# Charger.net
KiCad netlist of a schematic drawn in Altium Designer
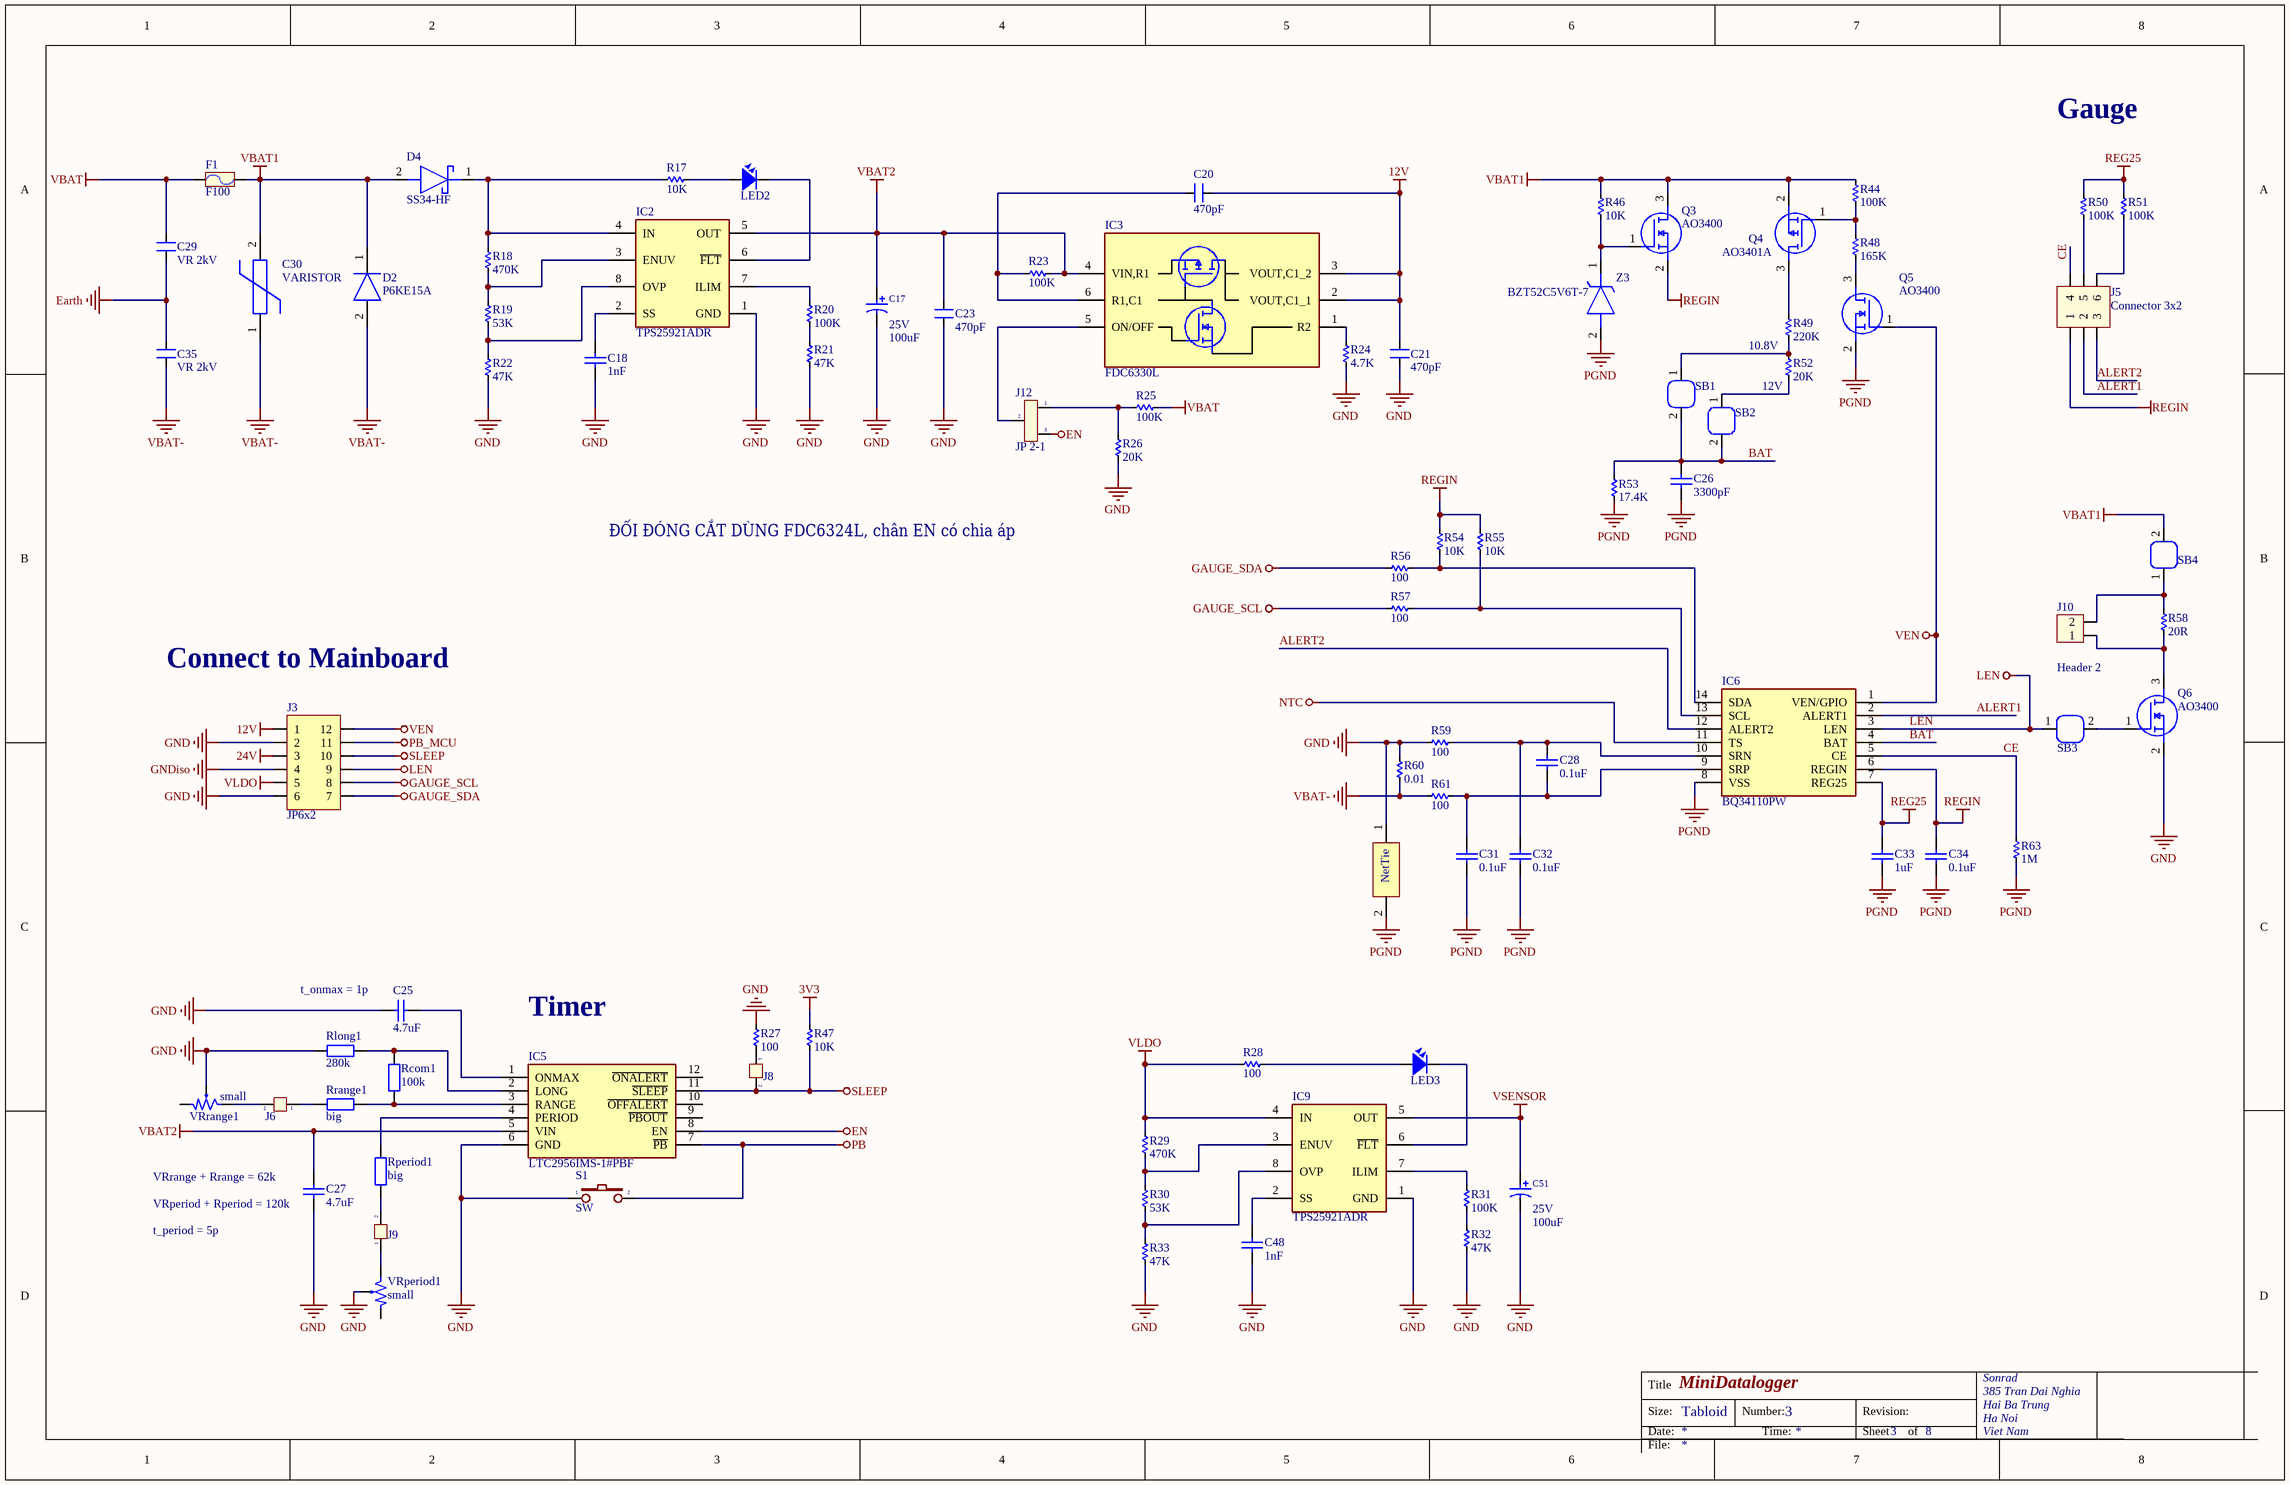
[diagram p0: Charger.SchDoc]

(export (version "E")
  (design (tool "Eeschema 10.0.6"))
  (components
    (comp (ref "*") (value "NetTie") (footprint "NetTie") (libsource (lib "PhanBach") (part "NetTie")))
    (comp (ref "C17")
      (value "100uF")
      (footprint "Cap SMD Tant")
      (description "Polarized Tanta Capacitor")
      (fields
        (field (name "MANUFACTURER") "FARNELL")
        (field (name "VOLT") "25V")
        (field (name "Comment") "100 uF 25V")
        (field (name "PUBLISHER") "Hoang Nguyen")
      )
      (libsource (lib "hphonglib") (part "Cap_Pol"))
    )
    (comp (ref "C18")
      (value "1nF")
      (footprint "0805 CAP")
      (fields (field (name "PUBLISHER") "Altium Limited"))
      (libsource (lib "ThinhNguyenLib") (part "CAP CERAMIC"))
    )
    (comp (ref "C20")
      (value "470pF")
      (footprint "SM-0805")
      (description "Cap SMD")
      (libsource (lib "hphonglib") (part "CM"))
    )
    (comp (ref "C21")
      (value "470pF")
      (footprint "SM-0805")
      (description "Cap SMD")
      (libsource (lib "hphonglib") (part "CM"))
    )
    (comp (ref "C23")
      (value "470pF")
      (footprint "SM-0805")
      (description "Cap SMD")
      (libsource (lib "hphonglib") (part "CM"))
    )
    (comp (ref "C25")
      (value "4.7uF")
      (footprint "0805 CAP")
      (fields (field (name "PUBLISHER") "Altium Limited"))
      (libsource (lib "ThinhNguyenLib") (part "CAP CERAMIC"))
    )
    (comp (ref "C26")
      (value "3300pF")
      (footprint "0805 CAP")
      (fields (field (name "PUBLISHER") "Altium Limited"))
      (libsource (lib "ThinhNguyenLib") (part "CAP CERAMIC"))
    )
    (comp (ref "C27")
      (value "4.7uF")
      (footprint "0805 CAP")
      (fields (field (name "PUBLISHER") "Altium Limited"))
      (libsource (lib "ThinhNguyenLib") (part "CAP CERAMIC"))
    )
    (comp (ref "C28")
      (value "0.1uF")
      (footprint "0805 CAP")
      (fields (field (name "PUBLISHER") "Altium Limited"))
      (libsource (lib "ThinhNguyenLib") (part "CAP CERAMIC"))
    )
    (comp (ref "C29")
      (value "VR 2kV")
      (footprint "CN3")
      (description "MOV")
      (fields (field (name "COPYRIGHT") "VanDungEvn"))
      (libsource (lib "library") (part "CN3"))
    )
    (comp (ref "C30")
      (value "VARISTOR")
      (footprint "CN2")
      (libsource (lib "ThinhNguyenLib") (part "VARISTOR"))
    )
    (comp (ref "C31")
      (value "0.1uF")
      (footprint "0805 CAP")
      (fields (field (name "PUBLISHER") "Altium Limited"))
      (libsource (lib "ThinhNguyenLib") (part "CAP CERAMIC"))
    )
    (comp (ref "C32")
      (value "0.1uF")
      (footprint "0805 CAP")
      (fields (field (name "PUBLISHER") "Altium Limited"))
      (libsource (lib "ThinhNguyenLib") (part "CAP CERAMIC"))
    )
    (comp (ref "C33")
      (value "1uF")
      (footprint "0805 CAP")
      (fields (field (name "PUBLISHER") "Altium Limited"))
      (libsource (lib "ThinhNguyenLib") (part "CAP CERAMIC"))
    )
    (comp (ref "C34")
      (value "0.1uF")
      (footprint "0805 CAP")
      (fields (field (name "PUBLISHER") "Altium Limited"))
      (libsource (lib "ThinhNguyenLib") (part "CAP CERAMIC"))
    )
    (comp (ref "C35")
      (value "VR 2kV")
      (footprint "CN3")
      (description "MOV")
      (fields (field (name "COPYRIGHT") "VanDungEvn"))
      (libsource (lib "library") (part "CN3"))
    )
    (comp (ref "C48")
      (value "1nF")
      (footprint "0805 CAP")
      (fields (field (name "PUBLISHER") "Altium Limited"))
      (libsource (lib "ThinhNguyenLib") (part "CAP CERAMIC"))
    )
    (comp (ref "C51")
      (value "100uF")
      (footprint "Cap SMD Tant")
      (description "Polarized Tanta Capacitor")
      (fields
        (field (name "MANUFACTURER") "FARNELL")
        (field (name "VOLT") "25V")
        (field (name "Comment") "100 uF 25V")
        (field (name "PUBLISHER") "Hoang Nguyen")
      )
      (libsource (lib "hphonglib") (part "Cap_Pol"))
    )
    (comp (ref "D2")
      (value "P6KE15A")
      (footprint "P6KE15A")
      (description "Diode")
      (fields (field (name "MOUSER PART NUMBER") "511-P6KE15A"))
      (libsource (lib "*") (part "P6KE15A"))
    )
    (comp (ref "D4")
      (value "SS34-HF")
      (footprint "SamacSys:DIOM5025X220N")
      (description "Schottky Diode")
      (fields (field (name "MOUSER PART NUMBER") "750-SS34-HF"))
      (libsource (lib "SamacSys") (part "SS34-HF"))
    )
    (comp (ref "F1")
      (value "F100")
      (footprint "Fuse1A")
      (description "Fuse")
      (fields (field (name "DESIGNED BY") "VanDungEvn"))
      (libsource (lib "HMI") (part "Fuse"))
    )
    (comp (ref "IC2")
      (value "TPS25921ADR")
      (footprint "SamacSys:SOIC127P600X175-8N")
      (description "Integrated Circuit")
      (fields (field (name "MOUSER PART NUMBER") "595-TPS25921ADR"))
      (libsource (lib "SamacSys") (part "TPS25921ADR"))
    )
    (comp (ref "IC3")
      (value "FDC6330L")
      (footprint "SamacSys:SOT95P280X110-6N")
      (description "Integrated Circuit")
      (fields (field (name "MOUSER PART NUMBER") "512-FDC6330L"))
      (libsource (lib "SamacSys") (part "FDC6330L"))
    )
    (comp (ref "IC5")
      (value "LTC2956IMS-1#PBF")
      (footprint "SamacSys:SOP65P490X110-12N")
      (description "Integrated Circuit")
      (fields (field (name "MOUSER PART NUMBER") "584-LTC2956IMS-1#PBF"))
      (libsource (lib "*") (part "LTC2956IMS-1#PBF"))
    )
    (comp (ref "IC6")
      (value "BQ34110PW")
      (footprint "SamacSys:SOP65P640X120-14N")
      (description "Integrated Circuit")
      (fields (field (name "MOUSER PART NUMBER") "595-BQ34110PW"))
      (libsource (lib "*") (part "BQ34110PW"))
    )
    (comp (ref "IC9")
      (value "TPS25921ADR")
      (footprint "SamacSys:SOIC127P600X175-8N")
      (description "Integrated Circuit")
      (fields (field (name "MOUSER PART NUMBER") "595-TPS25921ADR"))
      (libsource (lib "SamacSys") (part "TPS25921ADR"))
    )
    (comp (ref "J3")
      (value "JP6x2")
      (footprint "JP6-D2T")
      (description "WR-PHD 2.54 mm Dual Socket Header")
      (fields
        (field (name "MANUFACTURER") "Würth Elektronik eiSos GmbH")
        (field (name "PARTNO") "61301221821")
        (field (name "CREATED BY") "Karrer Zheng")
      )
      (libsource (lib "LIBRARY1") (part "JP6x2"))
    )
    (comp (ref "J5")
      (value "Connector 3x2")
      (footprint "JP3x2")
      (libsource (lib "syhaunguyen") (part "JP3x2"))
    )
    (comp (ref "J6") (value "Jumper 2") (footprint "JP2") (libsource (lib "library") (part "JP 2")))
    (comp (ref "J8") (value "Jumper 2") (footprint "JP2") (libsource (lib "") (part "JP 2_2")))
    (comp (ref "J9") (value "Jumper 2") (footprint "JP2") (libsource (lib "") (part "JP 2_1")))
    (comp (ref "J10")
      (value "Header 2")
      (footprint "HED2B")
      (description "Header 2 (Green)")
      (libsource (lib "syhaunguyen") (part "Hed2"))
    )
    (comp (ref "J12")
      (value "JP 2-1")
      (footprint "JP3")
      (description "Jumper 2-1")
      (libsource (lib "syhaunguyen") (part "JP 2-1"))
    )
    (comp (ref "LED2") (value "LED") (footprint "LED 3512") (libsource (lib "LIBRARY1") (part "LED SMD")))
    (comp (ref "LED3") (value "LED") (footprint "LED 3512") (libsource (lib "LIBRARY1") (part "LED SMD")))
    (comp (ref "Q3")
      (value "AO3400")
      (footprint "SamacSys:SOT95P280X125-3N")
      (description "MOSFET (N-Channel)")
      (libsource (lib "*") (part "AO3400"))
    )
    (comp (ref "Q4")
      (value "AO3401A")
      (footprint "SamacSys:SOT95P280X125-3N")
      (description "MOSFET (P-Channel)")
      (libsource (lib "*") (part "AO3401A"))
    )
    (comp (ref "Q5")
      (value "AO3400")
      (footprint "SamacSys:SOT95P280X125-3N")
      (description "MOSFET (N-Channel)")
      (libsource (lib "*") (part "AO3400"))
    )
    (comp (ref "Q6")
      (value "AO3400")
      (footprint "SamacSys:SOT95P280X125-3N")
      (description "MOSFET (N-Channel)")
      (libsource (lib "*") (part "AO3400"))
    )
    (comp (ref "R17")
      (value "10K")
      (footprint "RES-SMD-0805")
      (description "Resistor")
      (fields
        (field (name "MANUFACTURER") "Generic Components")
        (field (name "PUBLISHER") "Altium Hobart Technology Centre")
      )
      (libsource (lib "LIBRARY1") (part "Res-SMD"))
    )
    (comp (ref "R18")
      (value "470K")
      (footprint "RES-SMD-0805")
      (description "Resistor")
      (fields
        (field (name "MANUFACTURER") "Generic Components")
        (field (name "PUBLISHER") "Altium Hobart Technology Centre")
      )
      (libsource (lib "LIBRARY1") (part "Res-SMD"))
    )
    (comp (ref "R19")
      (value "53K")
      (footprint "RES-SMD-0805")
      (description "Resistor")
      (fields
        (field (name "MANUFACTURER") "Generic Components")
        (field (name "PUBLISHER") "Altium Hobart Technology Centre")
      )
      (libsource (lib "LIBRARY1") (part "Res-SMD"))
    )
    (comp (ref "R20")
      (value "100K")
      (footprint "RES-SMD-0805")
      (description "Resistor")
      (fields
        (field (name "MANUFACTURER") "Generic Components")
        (field (name "PUBLISHER") "Altium Hobart Technology Centre")
      )
      (libsource (lib "LIBRARY1") (part "Res-SMD"))
    )
    (comp (ref "R21")
      (value "47K")
      (footprint "RES-SMD-0805")
      (description "Resistor")
      (fields
        (field (name "MANUFACTURER") "Generic Components")
        (field (name "PUBLISHER") "Altium Hobart Technology Centre")
      )
      (libsource (lib "LIBRARY1") (part "Res-SMD"))
    )
    (comp (ref "R22")
      (value "47K")
      (footprint "RES-SMD-0805")
      (description "Resistor")
      (fields
        (field (name "MANUFACTURER") "Generic Components")
        (field (name "PUBLISHER") "Altium Hobart Technology Centre")
      )
      (libsource (lib "LIBRARY1") (part "Res-SMD"))
    )
    (comp (ref "R23")
      (value "100K")
      (footprint "RES-SMD-0805")
      (description "Resistor")
      (fields
        (field (name "MANUFACTURER") "Generic Components")
        (field (name "PUBLISHER") "Altium Hobart Technology Centre")
      )
      (libsource (lib "LIBRARY1") (part "Res-SMD"))
    )
    (comp (ref "R24")
      (value "4.7K")
      (footprint "RES-SMD-0805")
      (description "Resistor")
      (fields
        (field (name "MANUFACTURER") "Generic Components")
        (field (name "PUBLISHER") "Altium Hobart Technology Centre")
      )
      (libsource (lib "LIBRARY1") (part "Res-SMD"))
    )
    (comp (ref "R25")
      (value "100K")
      (footprint "RES-SMD-0805")
      (description "Resistor")
      (fields
        (field (name "MANUFACTURER") "Generic Components")
        (field (name "PUBLISHER") "Altium Hobart Technology Centre")
      )
      (libsource (lib "LIBRARY1") (part "Res-SMD"))
    )
    (comp (ref "R26")
      (value "20K")
      (footprint "RES-SMD-0805")
      (description "Resistor")
      (fields
        (field (name "MANUFACTURER") "Generic Components")
        (field (name "PUBLISHER") "Altium Hobart Technology Centre")
      )
      (libsource (lib "LIBRARY1") (part "Res-SMD"))
    )
    (comp (ref "R27")
      (value "100")
      (footprint "RES-SMD-0805")
      (description "Resistor")
      (fields
        (field (name "MANUFACTURER") "Generic Components")
        (field (name "PUBLISHER") "Altium Hobart Technology Centre")
      )
      (libsource (lib "LIBRARY1") (part "Res-SMD"))
    )
    (comp (ref "R28")
      (value "100")
      (footprint "RES-SMD-0805")
      (description "Resistor")
      (fields
        (field (name "MANUFACTURER") "Generic Components")
        (field (name "PUBLISHER") "Altium Hobart Technology Centre")
      )
      (libsource (lib "LIBRARY1") (part "Res-SMD"))
    )
    (comp (ref "R29")
      (value "470K")
      (footprint "RES-SMD-0805")
      (description "Resistor")
      (fields
        (field (name "MANUFACTURER") "Generic Components")
        (field (name "PUBLISHER") "Altium Hobart Technology Centre")
      )
      (libsource (lib "LIBRARY1") (part "Res-SMD"))
    )
    (comp (ref "R30")
      (value "53K")
      (footprint "RES-SMD-0805")
      (description "Resistor")
      (fields
        (field (name "MANUFACTURER") "Generic Components")
        (field (name "PUBLISHER") "Altium Hobart Technology Centre")
      )
      (libsource (lib "LIBRARY1") (part "Res-SMD"))
    )
    (comp (ref "R31")
      (value "100K")
      (footprint "RES-SMD-0805")
      (description "Resistor")
      (fields
        (field (name "MANUFACTURER") "Generic Components")
        (field (name "PUBLISHER") "Altium Hobart Technology Centre")
      )
      (libsource (lib "LIBRARY1") (part "Res-SMD"))
    )
    (comp (ref "R32")
      (value "47K")
      (footprint "RES-SMD-0805")
      (description "Resistor")
      (fields
        (field (name "MANUFACTURER") "Generic Components")
        (field (name "PUBLISHER") "Altium Hobart Technology Centre")
      )
      (libsource (lib "LIBRARY1") (part "Res-SMD"))
    )
    (comp (ref "R33")
      (value "47K")
      (footprint "RES-SMD-0805")
      (description "Resistor")
      (fields
        (field (name "MANUFACTURER") "Generic Components")
        (field (name "PUBLISHER") "Altium Hobart Technology Centre")
      )
      (libsource (lib "LIBRARY1") (part "Res-SMD"))
    )
    (comp (ref "R44")
      (value "100K")
      (footprint "RES-SMD-0805")
      (description "Resistor")
      (fields
        (field (name "MANUFACTURER") "Generic Components")
        (field (name "PUBLISHER") "Altium Hobart Technology Centre")
      )
      (libsource (lib "LIBRARY1") (part "Res-SMD"))
    )
    (comp (ref "R46")
      (value "10K")
      (footprint "RES-SMD-0805")
      (description "Resistor")
      (fields
        (field (name "MANUFACTURER") "Generic Components")
        (field (name "PUBLISHER") "Altium Hobart Technology Centre")
      )
      (libsource (lib "LIBRARY1") (part "Res-SMD"))
    )
    (comp (ref "R47")
      (value "10K")
      (footprint "RES-SMD-0805")
      (description "Resistor")
      (fields
        (field (name "MANUFACTURER") "Generic Components")
        (field (name "PUBLISHER") "Altium Hobart Technology Centre")
      )
      (libsource (lib "LIBRARY1") (part "Res-SMD"))
    )
    (comp (ref "R48")
      (value "165K")
      (footprint "RES-SMD-0805")
      (description "Resistor")
      (fields
        (field (name "MANUFACTURER") "Generic Components")
        (field (name "PUBLISHER") "Altium Hobart Technology Centre")
      )
      (libsource (lib "LIBRARY1") (part "Res-SMD"))
    )
    (comp (ref "R49")
      (value "220K")
      (footprint "RES-SMD-0805")
      (description "Resistor")
      (fields
        (field (name "MANUFACTURER") "Generic Components")
        (field (name "PUBLISHER") "Altium Hobart Technology Centre")
      )
      (libsource (lib "LIBRARY1") (part "Res-SMD"))
    )
    (comp (ref "R50")
      (value "100K")
      (footprint "RES-SMD-0805")
      (description "Resistor")
      (fields
        (field (name "MANUFACTURER") "Generic Components")
        (field (name "PUBLISHER") "Altium Hobart Technology Centre")
      )
      (libsource (lib "LIBRARY1") (part "Res-SMD"))
    )
    (comp (ref "R51")
      (value "100K")
      (footprint "RES-SMD-0805")
      (description "Resistor")
      (fields
        (field (name "MANUFACTURER") "Generic Components")
        (field (name "PUBLISHER") "Altium Hobart Technology Centre")
      )
      (libsource (lib "LIBRARY1") (part "Res-SMD"))
    )
    (comp (ref "R52")
      (value "20K")
      (footprint "RES-SMD-0805")
      (description "Resistor")
      (fields
        (field (name "MANUFACTURER") "Generic Components")
        (field (name "PUBLISHER") "Altium Hobart Technology Centre")
      )
      (libsource (lib "LIBRARY1") (part "Res-SMD"))
    )
    (comp (ref "R53")
      (value "17.4K")
      (footprint "RES-SMD-0805")
      (description "Resistor")
      (fields
        (field (name "MANUFACTURER") "Generic Components")
        (field (name "PUBLISHER") "Altium Hobart Technology Centre")
      )
      (libsource (lib "LIBRARY1") (part "Res-SMD"))
    )
    (comp (ref "R54")
      (value "10K")
      (footprint "RES-SMD-0805")
      (description "Resistor")
      (fields
        (field (name "MANUFACTURER") "Generic Components")
        (field (name "PUBLISHER") "Altium Hobart Technology Centre")
      )
      (libsource (lib "LIBRARY1") (part "Res-SMD"))
    )
    (comp (ref "R55")
      (value "10K")
      (footprint "RES-SMD-0805")
      (description "Resistor")
      (fields
        (field (name "MANUFACTURER") "Generic Components")
        (field (name "PUBLISHER") "Altium Hobart Technology Centre")
      )
      (libsource (lib "LIBRARY1") (part "Res-SMD"))
    )
    (comp (ref "R56")
      (value "100")
      (footprint "RES-SMD-0805")
      (description "Resistor")
      (fields
        (field (name "MANUFACTURER") "Generic Components")
        (field (name "PUBLISHER") "Altium Hobart Technology Centre")
      )
      (libsource (lib "LIBRARY1") (part "Res-SMD"))
    )
    (comp (ref "R57")
      (value "100")
      (footprint "RES-SMD-0805")
      (description "Resistor")
      (fields
        (field (name "MANUFACTURER") "Generic Components")
        (field (name "PUBLISHER") "Altium Hobart Technology Centre")
      )
      (libsource (lib "LIBRARY1") (part "Res-SMD"))
    )
    (comp (ref "R58")
      (value "20R")
      (footprint "RES-SMD-2512")
      (description "Resistor")
      (fields
        (field (name "MANUFACTURER") "Generic Components")
        (field (name "PUBLISHER") "Altium Hobart Technology Centre")
      )
      (libsource (lib "LIBRARY1") (part "Res-SMD"))
    )
    (comp (ref "R59")
      (value "100")
      (footprint "RES-SMD-0805")
      (description "Resistor")
      (fields
        (field (name "MANUFACTURER") "Generic Components")
        (field (name "PUBLISHER") "Altium Hobart Technology Centre")
      )
      (libsource (lib "LIBRARY1") (part "Res-SMD"))
    )
    (comp (ref "R60")
      (value "0.01")
      (footprint "RES-SMD-1210")
      (description "Resistor")
      (fields
        (field (name "MANUFACTURER") "Generic Components")
        (field (name "PUBLISHER") "Altium Hobart Technology Centre")
      )
      (libsource (lib "LIBRARY1") (part "Res-SMD"))
    )
    (comp (ref "R61")
      (value "100")
      (footprint "RES-SMD-0805")
      (description "Resistor")
      (fields
        (field (name "MANUFACTURER") "Generic Components")
        (field (name "PUBLISHER") "Altium Hobart Technology Centre")
      )
      (libsource (lib "LIBRARY1") (part "Res-SMD"))
    )
    (comp (ref "R63")
      (value "1M")
      (footprint "RES-SMD-0805")
      (description "Resistor")
      (fields
        (field (name "MANUFACTURER") "Generic Components")
        (field (name "PUBLISHER") "Altium Hobart Technology Centre")
      )
      (libsource (lib "LIBRARY1") (part "Res-SMD"))
    )
    (comp (ref "Rcom1")
      (value "100k")
      (footprint "0805 RESISTOR")
      (libsource (lib "ThinhNguyenLib") (part "RESISTOR"))
    )
    (comp (ref "Rlong1")
      (value "280k")
      (footprint "0805 RESISTOR")
      (libsource (lib "ThinhNguyenLib") (part "RESISTOR"))
    )
    (comp (ref "Rperiod1")
      (value "big")
      (footprint "0805 RESISTOR")
      (libsource (lib "ThinhNguyenLib") (part "RESISTOR"))
    )
    (comp (ref "Rrange1")
      (value "big")
      (footprint "0805 RESISTOR")
      (libsource (lib "ThinhNguyenLib") (part "RESISTOR"))
    )
    (comp (ref "S1")
      (value "SW")
      (footprint "SW2")
      (description "Switch button 2 pin")
      (libsource (lib "library") (part "SW2"))
    )
    (comp (ref "SB1")
      (value "Solder bridge")
      (footprint "Solder Bridge")
      (libsource (lib "PhanBach") (part "Solder bridge"))
    )
    (comp (ref "SB2")
      (value "Solder bridge")
      (footprint "Solder Bridge")
      (libsource (lib "PhanBach") (part "Solder bridge"))
    )
    (comp (ref "SB3")
      (value "Solder bridge")
      (footprint "Solder Bridge")
      (libsource (lib "PhanBach") (part "Solder bridge"))
    )
    (comp (ref "SB4")
      (value "Solder bridge")
      (footprint "Solder Bridge")
      (libsource (lib "PhanBach") (part "Solder bridge"))
    )
    (comp (ref "VRperiod1")
      (value "small")
      (footprint "VR1")
      (description "Var Resistor")
      (libsource (lib "library") (part "VR1"))
    )
    (comp (ref "VRrange1")
      (value "small")
      (footprint "VR1")
      (description "Var Resistor")
      (libsource (lib "library") (part "VR1"))
    )
    (comp (ref "Z3")
      (value "BZT52C5V6T-7")
      (footprint "SamacSys:SODFL1608X65N")
      (description "Zener Diode")
      (fields (field (name "MOUSER PART NUMBER") "621-BZT52C5V6T-7"))
      (libsource (lib "*") (part "BZT52C5V6T-7"))
    )
  )
  (nets
    (net (code "1") (name "/ALERT1") (class "Default")
      (node (ref "IC6") (pin "2") (pinfunction "ALERT1_2") (pintype "passive"))
      (node (ref "J5") (pin "5") (pinfunction "2_5") (pintype "passive"))
    )
    (net (code "2") (name "/ALERT2") (class "Default")
      (node (ref "IC6") (pin "12") (pinfunction "ALERT2_12") (pintype "passive"))
      (node (ref "J5") (pin "6") (pinfunction "3_6") (pintype "passive"))
    )
    (net (code "3") (name "/BAT") (class "Default")
      (node (ref "C26") (pin "2") (pinfunction "2_2") (pintype "passive"))
      (node (ref "IC6") (pin "4") (pinfunction "BAT_4") (pintype "passive"))
      (node (ref "R53") (pin "2") (pinfunction "2_2") (pintype "passive"))
      (node (ref "SB1") (pin "2") (pinfunction "42_2") (pintype "passive"))
      (node (ref "SB2") (pin "2") (pinfunction "42_2") (pintype "passive"))
    )
    (net (code "4") (name "/CE") (class "Default")
      (node (ref "IC6") (pin "5") (pinfunction "CE_5") (pintype "passive"))
      (node (ref "J5") (pin "4") (pinfunction "4_4") (pintype "passive"))
      (node (ref "R63") (pin "2") (pinfunction "2_2") (pintype "passive"))
    )
    (net (code "5") (name "3V3") (class "Default")
      (node (ref "R47") (pin "2") (pinfunction "2_2") (pintype "passive"))
    )
    (net (code "6") (name "12V") (class "Default")
      (node (ref "C20") (pin "2") (pinfunction "2_2") (pintype "passive"))
      (node (ref "C21") (pin "1") (pinfunction "1_1") (pintype "passive"))
      (node (ref "IC3") (pin "2") (pinfunction "VOUT,C1_1_2") (pintype "passive"))
      (node (ref "IC3") (pin "3") (pinfunction "VOUT,C1_2_3") (pintype "passive"))
      (node (ref "J3") (pin "1") (pinfunction "1_1") (pintype "passive"))
    )
    (net (code "7") (name "24V") (class "Default")
      (node (ref "J3") (pin "3") (pinfunction "3_3") (pintype "passive"))
    )
    (net (code "8") (name "EN") (class "Default")
      (node (ref "IC5") (pin "8") (pinfunction "EN_8") (pintype "passive"))
      (node (ref "J12") (pin "3") (pinfunction "3_3") (pintype "passive"))
    )
    (net (code "9") (name "Earth") (class "Default")
      (node (ref "C29") (pin "1") (pinfunction "1_1") (pintype "passive"))
      (node (ref "C35") (pin "2") (pinfunction "2_2") (pintype "passive"))
    )
    (net (code "10") (name "GAUGE_SCL") (class "Default")
      (node (ref "J3") (pin "8") (pinfunction "8_8") (pintype "passive"))
      (node (ref "R57") (pin "1") (pinfunction "1_1") (pintype "passive"))
    )
    (net (code "11") (name "GAUGE_SDA") (class "Default")
      (node (ref "J3") (pin "7") (pinfunction "7_7") (pintype "passive"))
      (node (ref "R56") (pin "1") (pinfunction "1_1") (pintype "passive"))
    )
    (net (code "12") (name "GND") (class "Default")
      (node (ref "*") (pin "1") (pinfunction "43_1") (pintype "passive"))
      (node (ref "C17") (pin "2") (pinfunction "2_2") (pintype "passive"))
      (node (ref "C18") (pin "2") (pinfunction "2_2") (pintype "passive"))
      (node (ref "C21") (pin "2") (pinfunction "2_2") (pintype "passive"))
      (node (ref "C23") (pin "2") (pinfunction "2_2") (pintype "passive"))
      (node (ref "C25") (pin "2") (pinfunction "2_2") (pintype "passive"))
      (node (ref "C27") (pin "1") (pinfunction "1_1") (pintype "passive"))
      (node (ref "C48") (pin "2") (pinfunction "2_2") (pintype "passive"))
      (node (ref "C51") (pin "2") (pinfunction "2_2") (pintype "passive"))
      (node (ref "IC2") (pin "1") (pinfunction "GND_1") (pintype "passive"))
      (node (ref "IC5") (pin "6") (pinfunction "GND_6") (pintype "passive"))
      (node (ref "IC9") (pin "1") (pinfunction "GND_1") (pintype "passive"))
      (node (ref "J3") (pin "2") (pinfunction "2_2") (pintype "passive"))
      (node (ref "J3") (pin "6") (pinfunction "6_6") (pintype "passive"))
      (node (ref "Q6") (pin "2") (pinfunction "S_2") (pintype "passive"))
      (node (ref "R21") (pin "1") (pinfunction "1_1") (pintype "passive"))
      (node (ref "R22") (pin "1") (pinfunction "1_1") (pintype "passive"))
      (node (ref "R24") (pin "1") (pinfunction "1_1") (pintype "passive"))
      (node (ref "R26") (pin "1") (pinfunction "1_1") (pintype "passive"))
      (node (ref "R27") (pin "2") (pinfunction "2_2") (pintype "passive"))
      (node (ref "R32") (pin "1") (pinfunction "1_1") (pintype "passive"))
      (node (ref "R33") (pin "1") (pinfunction "1_1") (pintype "passive"))
      (node (ref "R59") (pin "1") (pinfunction "1_1") (pintype "passive"))
      (node (ref "R60") (pin "1") (pinfunction "1_1") (pintype "passive"))
      (node (ref "Rlong1") (pin "1") (pinfunction "1_1") (pintype "passive"))
      (node (ref "S1") (pin "1") (pinfunction "1_1") (pintype "passive"))
      (node (ref "VRperiod1") (pin "2") (pinfunction "2_2") (pintype "passive"))
      (node (ref "VRrange1") (pin "2") (pinfunction "2_2") (pintype "passive"))
    )
    (net (code "13") (name "GNDiso") (class "Default")
      (node (ref "J3") (pin "4") (pinfunction "4_4") (pintype "passive"))
    )
    (net (code "14") (name "LEN") (class "Default")
      (node (ref "IC6") (pin "3") (pinfunction "LEN_3") (pintype "passive"))
      (node (ref "J3") (pin "9") (pinfunction "9_9") (pintype "passive"))
      (node (ref "SB3") (pin "1") (pinfunction "41_1") (pintype "passive"))
    )
    (net (code "15") (name "NTC") (class "Default")
      (node (ref "IC6") (pin "11") (pinfunction "TS_11") (pintype "passive"))
    )
    (net (code "16") (name "Net-(D4-K)") (class "Default")
      (node (ref "D4") (pin "1") (pinfunction "K_1") (pintype "passive"))
      (node (ref "IC2") (pin "4") (pinfunction "IN_4") (pintype "passive"))
      (node (ref "R17") (pin "1") (pinfunction "1_1") (pintype "passive"))
      (node (ref "R18") (pin "2") (pinfunction "2_2") (pintype "passive"))
    )
    (net (code "17") (name "Net-(IC2-ENUV)") (class "Default")
      (node (ref "IC2") (pin "3") (pinfunction "ENUV_3") (pintype "passive"))
      (node (ref "R18") (pin "1") (pinfunction "1_1") (pintype "passive"))
      (node (ref "R19") (pin "2") (pinfunction "2_2") (pintype "passive"))
    )
    (net (code "18") (name "Net-(IC2-ILIM)") (class "Default")
      (node (ref "IC2") (pin "7") (pinfunction "ILIM_7") (pintype "passive"))
      (node (ref "R20") (pin "2") (pinfunction "2_2") (pintype "passive"))
    )
    (net (code "19") (name "Net-(IC2-OVP)") (class "Default")
      (node (ref "IC2") (pin "8") (pinfunction "OVP_8") (pintype "passive"))
      (node (ref "R19") (pin "1") (pinfunction "1_1") (pintype "passive"))
      (node (ref "R22") (pin "2") (pinfunction "2_2") (pintype "passive"))
    )
    (net (code "20") (name "Net-(IC2-SS)") (class "Default")
      (node (ref "C18") (pin "1") (pinfunction "1_1") (pintype "passive"))
      (node (ref "IC2") (pin "2") (pinfunction "SS_2") (pintype "passive"))
    )
    (net (code "21") (name "Net-(IC2-~{FLT})") (class "Default")
      (node (ref "IC2") (pin "6") (pinfunction "~{FLT}_6") (pintype "passive"))
      (node (ref "LED2") (pin "2") (pinfunction "2_2") (pintype "passive"))
    )
    (net (code "22") (name "Net-(IC3-ON{slash}OFF)") (class "Default")
      (node (ref "IC3") (pin "5") (pinfunction "ON/OFF_5") (pintype "passive"))
      (node (ref "J12") (pin "2") (pinfunction "2_2") (pintype "passive"))
    )
    (net (code "23") (name "Net-(IC3-R1,C1)") (class "Default")
      (node (ref "C20") (pin "1") (pinfunction "1_1") (pintype "passive"))
      (node (ref "IC3") (pin "6") (pinfunction "R1,C1_6") (pintype "passive"))
      (node (ref "R23") (pin "2") (pinfunction "2_2") (pintype "passive"))
    )
    (net (code "24") (name "Net-(IC3-R2)") (class "Default")
      (node (ref "IC3") (pin "1") (pinfunction "R2_1") (pintype "passive"))
      (node (ref "R24") (pin "2") (pinfunction "2_2") (pintype "passive"))
    )
    (net (code "25") (name "Net-(IC5-LONG)") (class "Default")
      (node (ref "IC5") (pin "2") (pinfunction "LONG_2") (pintype "passive"))
      (node (ref "Rcom1") (pin "2") (pinfunction "2_2") (pintype "passive"))
      (node (ref "Rlong1") (pin "2") (pinfunction "2_2") (pintype "passive"))
    )
    (net (code "26") (name "Net-(IC5-ONMAX)") (class "Default")
      (node (ref "C25") (pin "1") (pinfunction "1_1") (pintype "passive"))
      (node (ref "IC5") (pin "1") (pinfunction "ONMAX_1") (pintype "passive"))
    )
    (net (code "27") (name "Net-(IC5-PERIOD)") (class "Default")
      (node (ref "IC5") (pin "4") (pinfunction "PERIOD_4") (pintype "passive"))
      (node (ref "Rperiod1") (pin "2") (pinfunction "2_2") (pintype "passive"))
    )
    (net (code "28") (name "Net-(IC5-RANGE)") (class "Default")
      (node (ref "IC5") (pin "3") (pinfunction "RANGE_3") (pintype "passive"))
      (node (ref "Rcom1") (pin "1") (pinfunction "1_1") (pintype "passive"))
      (node (ref "Rrange1") (pin "2") (pinfunction "2_2") (pintype "passive"))
    )
    (net (code "29") (name "Net-(IC6-SCL)") (class "Default")
      (node (ref "IC6") (pin "13") (pinfunction "SCL_13") (pintype "passive"))
      (node (ref "R55") (pin "1") (pinfunction "1_1") (pintype "passive"))
      (node (ref "R57") (pin "2") (pinfunction "2_2") (pintype "passive"))
    )
    (net (code "30") (name "Net-(IC6-SDA)") (class "Default")
      (node (ref "IC6") (pin "14") (pinfunction "SDA_14") (pintype "passive"))
      (node (ref "R54") (pin "1") (pinfunction "1_1") (pintype "passive"))
      (node (ref "R56") (pin "2") (pinfunction "2_2") (pintype "passive"))
    )
    (net (code "31") (name "Net-(IC6-SRN)") (class "Default")
      (node (ref "C28") (pin "2") (pinfunction "2_2") (pintype "passive"))
      (node (ref "C32") (pin "2") (pinfunction "2_2") (pintype "passive"))
      (node (ref "IC6") (pin "10") (pinfunction "SRN_10") (pintype "passive"))
      (node (ref "R59") (pin "2") (pinfunction "2_2") (pintype "passive"))
    )
    (net (code "32") (name "Net-(IC6-SRP)") (class "Default")
      (node (ref "C28") (pin "1") (pinfunction "1_1") (pintype "passive"))
      (node (ref "C31") (pin "2") (pinfunction "2_2") (pintype "passive"))
      (node (ref "IC6") (pin "9") (pinfunction "SRP_9") (pintype "passive"))
      (node (ref "R61") (pin "2") (pinfunction "2_2") (pintype "passive"))
    )
    (net (code "33") (name "Net-(IC9-ENUV)") (class "Default")
      (node (ref "IC9") (pin "3") (pinfunction "ENUV_3") (pintype "passive"))
      (node (ref "R29") (pin "1") (pinfunction "1_1") (pintype "passive"))
      (node (ref "R30") (pin "2") (pinfunction "2_2") (pintype "passive"))
    )
    (net (code "34") (name "Net-(IC9-ILIM)") (class "Default")
      (node (ref "IC9") (pin "7") (pinfunction "ILIM_7") (pintype "passive"))
      (node (ref "R31") (pin "2") (pinfunction "2_2") (pintype "passive"))
    )
    (net (code "35") (name "Net-(IC9-OVP)") (class "Default")
      (node (ref "IC9") (pin "8") (pinfunction "OVP_8") (pintype "passive"))
      (node (ref "R30") (pin "1") (pinfunction "1_1") (pintype "passive"))
      (node (ref "R33") (pin "2") (pinfunction "2_2") (pintype "passive"))
    )
    (net (code "36") (name "Net-(IC9-SS)") (class "Default")
      (node (ref "C48") (pin "1") (pinfunction "1_1") (pintype "passive"))
      (node (ref "IC9") (pin "2") (pinfunction "SS_2") (pintype "passive"))
    )
    (net (code "37") (name "Net-(IC9-~{FLT})") (class "Default")
      (node (ref "IC9") (pin "6") (pinfunction "~{FLT}_6") (pintype "passive"))
      (node (ref "LED3") (pin "2") (pinfunction "2_2") (pintype "passive"))
    )
    (net (code "38") (name "Net-(J5-5)") (class "Default")
      (node (ref "J5") (pin "2") (pinfunction "5_2") (pintype "passive"))
      (node (ref "R50") (pin "1") (pinfunction "1_1") (pintype "passive"))
    )
    (net (code "39") (name "Net-(J5-6)") (class "Default")
      (node (ref "J5") (pin "3") (pinfunction "6_3") (pintype "passive"))
      (node (ref "R51") (pin "1") (pinfunction "1_1") (pintype "passive"))
    )
    (net (code "40") (name "Net-(J6-Pad1)") (class "Default")
      (node (ref "J6") (pin "1") (pinfunction "1_1") (pintype "passive"))
      (node (ref "Rrange1") (pin "1") (pinfunction "1_1") (pintype "passive"))
    )
    (net (code "41") (name "Net-(J6-Pad2)") (class "Default")
      (node (ref "J6") (pin "2") (pinfunction "2_2") (pintype "passive"))
      (node (ref "VRrange1") (pin "3") (pinfunction "3_3") (pintype "passive"))
    )
    (net (code "42") (name "Net-(J8-Pad1)") (class "Default")
      (node (ref "J8") (pin "1") (pinfunction "1_1") (pintype "passive"))
      (node (ref "R27") (pin "1") (pinfunction "1_1") (pintype "passive"))
    )
    (net (code "43") (name "Net-(J9-Pad1)") (class "Default")
      (node (ref "J9") (pin "1") (pinfunction "1_1") (pintype "passive"))
      (node (ref "VRperiod1") (pin "3") (pinfunction "3_3") (pintype "passive"))
    )
    (net (code "44") (name "Net-(J9-Pad2)") (class "Default")
      (node (ref "J9") (pin "2") (pinfunction "2_2") (pintype "passive"))
      (node (ref "Rperiod1") (pin "1") (pinfunction "1_1") (pintype "passive"))
    )
    (net (code "45") (name "Net-(J12-Pad1)") (class "Default")
      (node (ref "J12") (pin "1") (pinfunction "1_1") (pintype "passive"))
      (node (ref "R25") (pin "2") (pinfunction "2_2") (pintype "passive"))
      (node (ref "R26") (pin "2") (pinfunction "2_2") (pintype "passive"))
    )
    (net (code "46") (name "Net-(LED2-Pad1)") (class "Default")
      (node (ref "LED2") (pin "1") (pinfunction "1_1") (pintype "passive"))
      (node (ref "R17") (pin "2") (pinfunction "2_2") (pintype "passive"))
    )
    (net (code "47") (name "Net-(LED3-Pad1)") (class "Default")
      (node (ref "LED3") (pin "1") (pinfunction "1_1") (pintype "passive"))
      (node (ref "R28") (pin "2") (pinfunction "2_2") (pintype "passive"))
    )
    (net (code "48") (name "Net-(Q3-G)") (class "Default")
      (node (ref "Q3") (pin "1") (pinfunction "G_1") (pintype "passive"))
      (node (ref "R46") (pin "1") (pinfunction "1_1") (pintype "passive"))
      (node (ref "Z3") (pin "1") (pinfunction "K_1") (pintype "passive"))
    )
    (net (code "49") (name "Net-(Q4-D)") (class "Default")
      (node (ref "Q4") (pin "3") (pinfunction "D_3") (pintype "passive"))
      (node (ref "R49") (pin "2") (pinfunction "2_2") (pintype "passive"))
    )
    (net (code "50") (name "Net-(Q4-G)") (class "Default")
      (node (ref "Q4") (pin "1") (pinfunction "G_1") (pintype "passive"))
      (node (ref "R44") (pin "1") (pinfunction "1_1") (pintype "passive"))
      (node (ref "R48") (pin "2") (pinfunction "2_2") (pintype "passive"))
    )
    (net (code "51") (name "Net-(Q5-D)") (class "Default")
      (node (ref "Q5") (pin "3") (pinfunction "D_3") (pintype "passive"))
      (node (ref "R48") (pin "1") (pinfunction "1_1") (pintype "passive"))
    )
    (net (code "52") (name "Net-(Q6-D)") (class "Default")
      (node (ref "J10") (pin "1") (pinfunction "1_1") (pintype "passive"))
      (node (ref "Q6") (pin "3") (pinfunction "D_3") (pintype "passive"))
      (node (ref "R58") (pin "1") (pinfunction "1_1") (pintype "passive"))
    )
    (net (code "53") (name "Net-(Q6-G)") (class "Default")
      (node (ref "Q6") (pin "1") (pinfunction "G_1") (pintype "passive"))
      (node (ref "SB3") (pin "2") (pinfunction "42_2") (pintype "passive"))
    )
    (net (code "54") (name "Net-(R20-Pad1)") (class "Default")
      (node (ref "R20") (pin "1") (pinfunction "1_1") (pintype "passive"))
      (node (ref "R21") (pin "2") (pinfunction "2_2") (pintype "passive"))
    )
    (net (code "55") (name "Net-(R31-Pad1)") (class "Default")
      (node (ref "R31") (pin "1") (pinfunction "1_1") (pintype "passive"))
      (node (ref "R32") (pin "2") (pinfunction "2_2") (pintype "passive"))
    )
    (net (code "56") (name "Net-(SB1-41)") (class "Default")
      (node (ref "R49") (pin "1") (pinfunction "1_1") (pintype "passive"))
      (node (ref "R52") (pin "2") (pinfunction "2_2") (pintype "passive"))
      (node (ref "SB1") (pin "1") (pinfunction "41_1") (pintype "passive"))
    )
    (net (code "57") (name "Net-(SB2-41)") (class "Default")
      (node (ref "R52") (pin "1") (pinfunction "1_1") (pintype "passive"))
      (node (ref "SB2") (pin "1") (pinfunction "41_1") (pintype "passive"))
    )
    (net (code "58") (name "Net-(SB4-41)") (class "Default")
      (node (ref "J10") (pin "2") (pinfunction "2_2") (pintype "passive"))
      (node (ref "R58") (pin "2") (pinfunction "2_2") (pintype "passive"))
      (node (ref "SB4") (pin "1") (pinfunction "41_1") (pintype "passive"))
    )
    (net (code "59") (name "PB") (class "Default")
      (node (ref "IC5") (pin "7") (pinfunction "~{PB}_7") (pintype "passive"))
      (node (ref "S1") (pin "2") (pinfunction "2_2") (pintype "passive"))
    )
    (net (code "60") (name "PB_MCU") (class "Default")
      (node (ref "J3") (pin "11") (pinfunction "11_11") (pintype "passive"))
    )
    (net (code "61") (name "PGND") (class "Default")
      (node (ref "*") (pin "2") (pinfunction "2_2") (pintype "passive"))
      (node (ref "C26") (pin "1") (pinfunction "1_1") (pintype "passive"))
      (node (ref "C31") (pin "1") (pinfunction "1_1") (pintype "passive"))
      (node (ref "C32") (pin "1") (pinfunction "1_1") (pintype "passive"))
      (node (ref "C33") (pin "1") (pinfunction "1_1") (pintype "passive"))
      (node (ref "C34") (pin "1") (pinfunction "1_1") (pintype "passive"))
      (node (ref "IC6") (pin "8") (pinfunction "VSS_8") (pintype "passive"))
      (node (ref "Q5") (pin "2") (pinfunction "S_2") (pintype "passive"))
      (node (ref "R53") (pin "1") (pinfunction "1_1") (pintype "passive"))
      (node (ref "R63") (pin "1") (pinfunction "1_1") (pintype "passive"))
      (node (ref "Z3") (pin "2") (pinfunction "A_2") (pintype "passive"))
    )
    (net (code "62") (name "REG25") (class "Default")
      (node (ref "C33") (pin "2") (pinfunction "2_2") (pintype "passive"))
      (node (ref "IC6") (pin "7") (pinfunction "REG25_7") (pintype "passive"))
      (node (ref "R50") (pin "2") (pinfunction "2_2") (pintype "passive"))
      (node (ref "R51") (pin "2") (pinfunction "2_2") (pintype "passive"))
    )
    (net (code "63") (name "REGIN") (class "Default")
      (node (ref "C34") (pin "2") (pinfunction "2_2") (pintype "passive"))
      (node (ref "IC6") (pin "6") (pinfunction "REGIN_6") (pintype "passive"))
      (node (ref "J5") (pin "1") (pinfunction "1_1") (pintype "passive"))
      (node (ref "Q3") (pin "2") (pinfunction "S_2") (pintype "passive"))
      (node (ref "R54") (pin "2") (pinfunction "2_2") (pintype "passive"))
      (node (ref "R55") (pin "2") (pinfunction "2_2") (pintype "passive"))
    )
    (net (code "64") (name "SLEEP") (class "Default")
      (node (ref "IC5") (pin "11") (pinfunction "~{SLEEP}_11") (pintype "passive"))
      (node (ref "J3") (pin "10") (pinfunction "10_10") (pintype "passive"))
      (node (ref "J8") (pin "2") (pinfunction "2_2") (pintype "passive"))
      (node (ref "R47") (pin "1") (pinfunction "1_1") (pintype "passive"))
    )
    (net (code "65") (name "VBAT") (class "Default")
      (node (ref "C29") (pin "2") (pinfunction "2_2") (pintype "passive"))
      (node (ref "F1") (pin "1") (pinfunction "1_1") (pintype "passive"))
      (node (ref "R25") (pin "1") (pinfunction "1_1") (pintype "passive"))
    )
    (net (code "66") (name "VBAT-") (class "Default")
      (node (ref "C30") (pin "1") (pinfunction "1_1") (pintype "passive"))
      (node (ref "C35") (pin "1") (pinfunction "1_1") (pintype "passive"))
      (node (ref "D2") (pin "2") (pinfunction "A_2") (pintype "passive"))
      (node (ref "R60") (pin "2") (pinfunction "2_2") (pintype "passive"))
      (node (ref "R61") (pin "1") (pinfunction "1_1") (pintype "passive"))
    )
    (net (code "67") (name "VBAT1") (class "Default")
      (node (ref "C30") (pin "2") (pinfunction "2_2") (pintype "passive"))
      (node (ref "D2") (pin "1") (pinfunction "K_1") (pintype "passive"))
      (node (ref "D4") (pin "2") (pinfunction "A_2") (pintype "passive"))
      (node (ref "F1") (pin "2") (pinfunction "2_2") (pintype "passive"))
      (node (ref "Q3") (pin "3") (pinfunction "D_3") (pintype "passive"))
      (node (ref "Q4") (pin "2") (pinfunction "S_2") (pintype "passive"))
      (node (ref "R44") (pin "2") (pinfunction "2_2") (pintype "passive"))
      (node (ref "R46") (pin "2") (pinfunction "2_2") (pintype "passive"))
      (node (ref "SB4") (pin "2") (pinfunction "42_2") (pintype "passive"))
    )
    (net (code "68") (name "VBAT2") (class "Default")
      (node (ref "C17") (pin "1") (pinfunction "1_1") (pintype "passive"))
      (node (ref "C23") (pin "1") (pinfunction "1_1") (pintype "passive"))
      (node (ref "C27") (pin "2") (pinfunction "2_2") (pintype "passive"))
      (node (ref "IC2") (pin "5") (pinfunction "OUT_5") (pintype "passive"))
      (node (ref "IC3") (pin "4") (pinfunction "VIN,R1_4") (pintype "passive"))
      (node (ref "IC5") (pin "5") (pinfunction "VIN_5") (pintype "passive"))
      (node (ref "R23") (pin "1") (pinfunction "1_1") (pintype "passive"))
    )
    (net (code "69") (name "VEN") (class "Default")
      (node (ref "IC6") (pin "1") (pinfunction "VEN/GPIO_1") (pintype "passive"))
      (node (ref "J3") (pin "12") (pinfunction "12_12") (pintype "passive"))
      (node (ref "Q5") (pin "1") (pinfunction "G_1") (pintype "passive"))
    )
    (net (code "70") (name "VLDO") (class "Default")
      (node (ref "IC9") (pin "4") (pinfunction "IN_4") (pintype "passive"))
      (node (ref "J3") (pin "5") (pinfunction "5_5") (pintype "passive"))
      (node (ref "R28") (pin "1") (pinfunction "1_1") (pintype "passive"))
      (node (ref "R29") (pin "2") (pinfunction "2_2") (pintype "passive"))
    )
    (net (code "71") (name "VSENSOR") (class "Default")
      (node (ref "C51") (pin "1") (pinfunction "1_1") (pintype "passive"))
      (node (ref "IC9") (pin "5") (pinfunction "OUT_5") (pintype "passive"))
    )
    (net (code "72") (name "unconnected-(IC5-~{OFFALERT}-Pad10)") (class "Default")
      (node (ref "IC5") (pin "10") (pinfunction "~{OFFALERT}_10") (pintype "passive"))
    )
    (net (code "73") (name "unconnected-(IC5-~{ONALERT}-Pad12)") (class "Default")
      (node (ref "IC5") (pin "12") (pinfunction "~{ONALERT}_12") (pintype "passive"))
    )
    (net (code "74") (name "unconnected-(IC5-~{PBOUT}-Pad9)") (class "Default")
      (node (ref "IC5") (pin "9") (pinfunction "~{PBOUT}_9") (pintype "passive"))
    )
    (net (code "75") (name "unconnected-(VRperiod1-Pad1)") (class "Default")
      (node (ref "VRperiod1") (pin "1") (pinfunction "1_1") (pintype "passive"))
    )
    (net (code "76") (name "unconnected-(VRrange1-Pad1)") (class "Default")
      (node (ref "VRrange1") (pin "1") (pinfunction "1_1") (pintype "passive"))
    )
  )
)
